# Termination_connector.net
KiCad netlist of a schematic drawn in Altium Designer
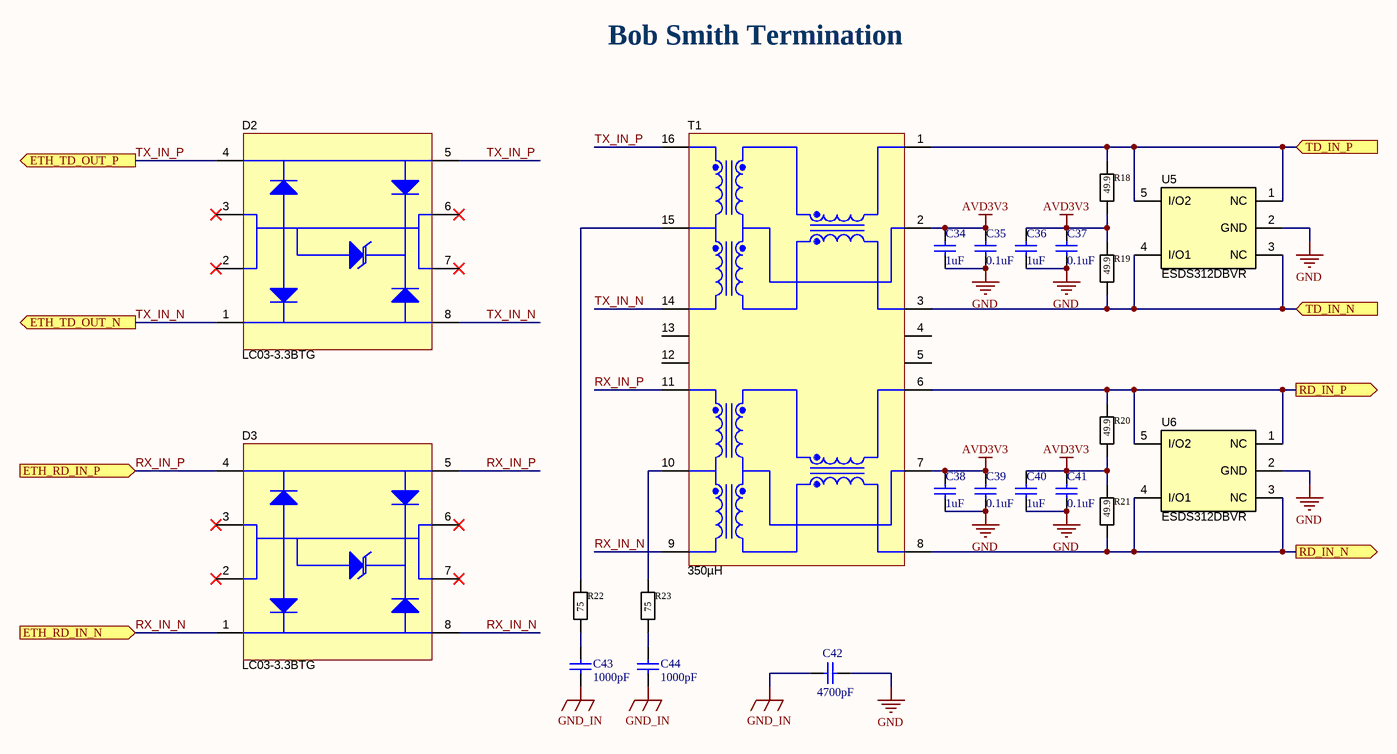
[diagram p0: Termination,connector.SchDoc]

(export (version "E")
  (design (tool "Eeschema 10.0.6"))
  (components
    (comp (ref "C34")
      (value "1uF")
      (footprint "CAPC1005X61USR")
      (description "CAP CER 1UF 16V X5R 0402")
      (fields
        (field (name "MANUFACTURER") "Samsung Electro-Mechanics")
        (field (name "MANUFACTURER PART NUMBER") "CL05A105KO5NNNC")
      )
      (libsource (lib "AA-Design-Challenge") (part "Cap"))
    )
    (comp (ref "C35")
      (value "0.1uF")
      (footprint "CAPC1005X61USR")
      (description "CAP CER 0.1UF 50V X7R 0402")
      (fields
        (field (name "MANUFACTURER") "TDK Corporation")
        (field (name "MANUFACTURER PART NUMBER") "CGA2B3X7R1H104K050BB")
      )
      (libsource (lib "AA-Design-Challenge") (part "Cap"))
    )
    (comp (ref "C36")
      (value "1uF")
      (footprint "CAPC1005X61USR")
      (description "CAP CER 1UF 16V X5R 0402")
      (fields
        (field (name "MANUFACTURER") "Samsung Electro-Mechanics")
        (field (name "MANUFACTURER PART NUMBER") "CL05A105KO5NNNC")
      )
      (libsource (lib "AA-Design-Challenge") (part "Cap"))
    )
    (comp (ref "C37")
      (value "0.1uF")
      (footprint "CAPC1005X61USR")
      (description "CAP CER 0.1UF 50V X7R 0402")
      (fields
        (field (name "MANUFACTURER") "TDK Corporation")
        (field (name "MANUFACTURER PART NUMBER") "CGA2B3X7R1H104K050BB")
      )
      (libsource (lib "AA-Design-Challenge") (part "Cap"))
    )
    (comp (ref "C38")
      (value "1uF")
      (footprint "CAPC1005X61USR")
      (description "CAP CER 1UF 16V X5R 0402")
      (fields
        (field (name "MANUFACTURER") "Samsung Electro-Mechanics")
        (field (name "MANUFACTURER PART NUMBER") "CL05A105KO5NNNC")
      )
      (libsource (lib "AA-Design-Challenge") (part "Cap"))
    )
    (comp (ref "C39")
      (value "0.1uF")
      (footprint "CAPC1005X61USR")
      (description "CAP CER 0.1UF 50V X7R 0402")
      (fields
        (field (name "MANUFACTURER") "TDK Corporation")
        (field (name "MANUFACTURER PART NUMBER") "CGA2B3X7R1H104K050BB")
      )
      (libsource (lib "AA-Design-Challenge") (part "Cap"))
    )
    (comp (ref "C40")
      (value "1uF")
      (footprint "CAPC1005X61USR")
      (description "CAP CER 1UF 16V X5R 0402")
      (fields
        (field (name "MANUFACTURER") "Samsung Electro-Mechanics")
        (field (name "MANUFACTURER PART NUMBER") "CL05A105KO5NNNC")
      )
      (libsource (lib "AA-Design-Challenge") (part "Cap"))
    )
    (comp (ref "C41")
      (value "0.1uF")
      (footprint "CAPC1005X61USR")
      (description "CAP CER 0.1UF 50V X7R 0402")
      (fields
        (field (name "MANUFACTURER") "TDK Corporation")
        (field (name "MANUFACTURER PART NUMBER") "CGA2B3X7R1H104K050BB")
      )
      (libsource (lib "AA-Design-Challenge") (part "Cap"))
    )
    (comp (ref "C42")
      (value "4700pF")
      (footprint "CAPC4532X200N")
      (description "CAP CER 4700PF 2KV X7R 1812")
      (fields
        (field (name "MANUFACTURER") "Murata Electronics")
        (field (name "MANUFACTURER PART NUMBER") "GR443DR73D472KW01L")
      )
      (libsource (lib "AA-Design-Challenge") (part "Cap"))
    )
    (comp (ref "C43")
      (value "1000pF")
      (footprint "CAPC1005X61USR")
      (description "CAP CER 1000PF 25V X7R 0402")
      (fields
        (field (name "MANUFACTURER") "KEMET")
        (field (name "MANUFACTURER PART NUMBER") "C0402C102K3RACTU")
      )
      (libsource (lib "AA-Design-Challenge") (part "Cap"))
    )
    (comp (ref "C44")
      (value "1000pF")
      (footprint "CAPC1005X61USR")
      (description "CAP CER 1000PF 25V X7R 0402")
      (fields
        (field (name "MANUFACTURER") "KEMET")
        (field (name "MANUFACTURER PART NUMBER") "C0402C102K3RACTU")
      )
      (libsource (lib "AA-Design-Challenge") (part "Cap"))
    )
    (comp (ref "D2")
      (value "LC03-3.3BTG")
      (footprint "SOIC127P600X175-8N")
      (description "Diode, TVS, Uni, 3.3 V, 17 Vc, 3300 W, 150 A, SOIC-8")
      (fields (field (name "MANUFACTURER") "Littelfuse"))
      (libsource (lib "AA-Design-Challenge") (part "CMP-0085616-1"))
    )
    (comp (ref "D3")
      (value "LC03-3.3BTG")
      (footprint "SOIC127P600X175-8N")
      (description "Diode, TVS, Uni, 3.3 V, 17 Vc, 3300 W, 150 A, SOIC-8")
      (fields (field (name "MANUFACTURER") "Littelfuse"))
      (libsource (lib "AA-Design-Challenge") (part "CMP-0085616-1"))
    )
    (comp (ref "R18")
      (value "49.9")
      (footprint "RESC1005X40USR")
      (description "RES SMD 49.9 OHM 1% 1/16W 0402")
      (fields
        (field (name "MANUFACTURER") "Yageo")
        (field (name "MANUFACTURER PART NUMBER") "RC0402FR-0749R9L")
      )
      (libsource (lib "AA-Design-Challenge") (part "R"))
    )
    (comp (ref "R19")
      (value "49.9")
      (footprint "RESC1005X40USR")
      (description "RES SMD 49.9 OHM 1% 1/16W 0402")
      (fields
        (field (name "MANUFACTURER") "Yageo")
        (field (name "MANUFACTURER PART NUMBER") "RC0402FR-0749R9L")
      )
      (libsource (lib "AA-Design-Challenge") (part "R"))
    )
    (comp (ref "R20")
      (value "49.9")
      (footprint "RESC1005X40USR")
      (description "RES SMD 49.9 OHM 1% 1/16W 0402")
      (fields
        (field (name "MANUFACTURER") "Yageo")
        (field (name "MANUFACTURER PART NUMBER") "RC0402FR-0749R9L")
      )
      (libsource (lib "AA-Design-Challenge") (part "R"))
    )
    (comp (ref "R21")
      (value "49.9")
      (footprint "RESC1005X40USR")
      (description "RES SMD 49.9 OHM 1% 1/16W 0402")
      (fields
        (field (name "MANUFACTURER") "Yageo")
        (field (name "MANUFACTURER PART NUMBER") "RC0402FR-0749R9L")
      )
      (libsource (lib "AA-Design-Challenge") (part "R"))
    )
    (comp (ref "R22")
      (value "75")
      (footprint "RESC1005X40USR")
      (description "RES SMD 75 OHM 1% 1/10W 0402")
      (fields
        (field (name "MANUFACTURER") "Panasonic Electronic Components")
        (field (name "MANUFACTURER PART NUMBER") "ERJ-2RKF75R0X")
      )
      (libsource (lib "AA-Design-Challenge") (part "R"))
    )
    (comp (ref "R23")
      (value "75")
      (footprint "RESC1005X40USR")
      (description "RES SMD 75 OHM 1% 1/10W 0402")
      (fields
        (field (name "MANUFACTURER") "Panasonic Electronic Components")
        (field (name "MANUFACTURER PART NUMBER") "ERJ-2RKF75R0X")
      )
      (libsource (lib "AA-Design-Challenge") (part "R"))
    )
    (comp (ref "T1")
      (value "~")
      (footprint "HX1198FNLT_PUL")
      (description "Transformer, 350 uH, SMT")
      (fields
        (field (name "MANUFACTURER PART NUMBER") "HX1198FNLT")
        (field (name "VALUEDISPLAYED") "350µH")
        (field (name "MANUFACTURER") "Pulse Engineering")
        (field (name "SYMBOLCREATOR") "Altium")
        (field (name "PUBLISHER") "Texas Instruments")
      )
      (libsource (lib "AA-Design-Challenge") (part "HX1198FNLT"))
    )
    (comp (ref "U5")
      (value "ESDS312DBVR")
      (footprint "SOT23-5")
      (description "FAMILY OF UNI-DIRECTIONAL SURGE")
      (fields
        (field (name "DIGI-KEY PART NUMBER") "296-51112-2-ND")
        (field (name "MANUFACTURER") "Texas Instruments")
        (field (name "MANUFACTURER PART NUMBER") "ESDS312DBVR")
      )
      (libsource (lib "AA-Design-Challenge") (part "ESDS312DBVR"))
    )
    (comp (ref "U6")
      (value "ESDS312DBVR")
      (footprint "SOT23-5")
      (description "FAMILY OF UNI-DIRECTIONAL SURGE")
      (fields
        (field (name "DIGI-KEY PART NUMBER") "296-51112-2-ND")
        (field (name "MANUFACTURER") "Texas Instruments")
        (field (name "MANUFACTURER PART NUMBER") "ESDS312DBVR")
      )
      (libsource (lib "AA-Design-Challenge") (part "ESDS312DBVR"))
    )
  )
  (nets
    (net (code "1") (name "/RD_IN_N") (class "Default")
      (node (ref "R21") (pin "2") (pintype "passive"))
      (node (ref "T1") (pin "8") (pinfunction "RD-_8") (pintype "passive"))
      (node (ref "U6") (pin "3") (pinfunction "NC_3") (pintype "passive"))
      (node (ref "U6") (pin "4") (pinfunction "I/O1_4") (pintype "passive"))
    )
    (net (code "2") (name "/RD_IN_P") (class "Default")
      (node (ref "R20") (pin "1") (pintype "passive"))
      (node (ref "T1") (pin "6") (pinfunction "RD+_6") (pintype "passive"))
      (node (ref "U6") (pin "1") (pinfunction "NC_1") (pintype "passive"))
      (node (ref "U6") (pin "5") (pinfunction "I/O2_5") (pintype "passive"))
    )
    (net (code "3") (name "/RX_IN_N") (class "Default")
      (node (ref "D3") (pin "1") (pinfunction "1_1") (pintype "passive"))
      (node (ref "D3") (pin "8") (pinfunction "8_8") (pintype "passive"))
      (node (ref "T1") (pin "9") (pinfunction "RX-_9") (pintype "passive"))
    )
    (net (code "4") (name "/RX_IN_P") (class "Default")
      (node (ref "D3") (pin "4") (pinfunction "4_4") (pintype "passive"))
      (node (ref "D3") (pin "5") (pinfunction "5_5") (pintype "passive"))
      (node (ref "T1") (pin "11") (pinfunction "RX+_11") (pintype "passive"))
    )
    (net (code "5") (name "/TD_IN_N") (class "Default")
      (node (ref "R19") (pin "2") (pintype "passive"))
      (node (ref "T1") (pin "3") (pinfunction "TD-_3") (pintype "passive"))
      (node (ref "U5") (pin "3") (pinfunction "NC_3") (pintype "passive"))
      (node (ref "U5") (pin "4") (pinfunction "I/O1_4") (pintype "passive"))
    )
    (net (code "6") (name "/TD_IN_P") (class "Default")
      (node (ref "R18") (pin "1") (pintype "passive"))
      (node (ref "T1") (pin "1") (pinfunction "TD+_1") (pintype "passive"))
      (node (ref "U5") (pin "1") (pinfunction "NC_1") (pintype "passive"))
      (node (ref "U5") (pin "5") (pinfunction "I/O2_5") (pintype "passive"))
    )
    (net (code "7") (name "/TX_IN_N") (class "Default")
      (node (ref "D2") (pin "1") (pinfunction "1_1") (pintype "passive"))
      (node (ref "D2") (pin "8") (pinfunction "8_8") (pintype "passive"))
      (node (ref "T1") (pin "14") (pinfunction "TX-_14") (pintype "passive"))
    )
    (net (code "8") (name "/TX_IN_P") (class "Default")
      (node (ref "D2") (pin "4") (pinfunction "4_4") (pintype "passive"))
      (node (ref "D2") (pin "5") (pinfunction "5_5") (pintype "passive"))
      (node (ref "T1") (pin "16") (pinfunction "TX+_16") (pintype "passive"))
    )
    (net (code "9") (name "AVD3V3") (class "Default")
      (node (ref "C34") (pin "2") (pinfunction "2_2") (pintype "passive"))
      (node (ref "C35") (pin "1") (pinfunction "1_1") (pintype "passive"))
      (node (ref "C36") (pin "2") (pinfunction "2_2") (pintype "passive"))
      (node (ref "C37") (pin "1") (pinfunction "1_1") (pintype "passive"))
      (node (ref "C38") (pin "2") (pinfunction "2_2") (pintype "passive"))
      (node (ref "C39") (pin "1") (pinfunction "1_1") (pintype "passive"))
      (node (ref "C40") (pin "2") (pinfunction "2_2") (pintype "passive"))
      (node (ref "C41") (pin "1") (pinfunction "1_1") (pintype "passive"))
      (node (ref "R18") (pin "2") (pintype "passive"))
      (node (ref "R19") (pin "1") (pintype "passive"))
      (node (ref "R20") (pin "2") (pintype "passive"))
      (node (ref "R21") (pin "1") (pintype "passive"))
      (node (ref "T1") (pin "2") (pinfunction "TCT_2") (pintype "passive"))
      (node (ref "T1") (pin "7") (pinfunction "RCT_7") (pintype "passive"))
    )
    (net (code "10") (name "GND") (class "Default")
      (node (ref "C34") (pin "1") (pinfunction "1_1") (pintype "passive"))
      (node (ref "C35") (pin "2") (pinfunction "2_2") (pintype "passive"))
      (node (ref "C36") (pin "1") (pinfunction "1_1") (pintype "passive"))
      (node (ref "C37") (pin "2") (pinfunction "2_2") (pintype "passive"))
      (node (ref "C38") (pin "1") (pinfunction "1_1") (pintype "passive"))
      (node (ref "C39") (pin "2") (pinfunction "2_2") (pintype "passive"))
      (node (ref "C40") (pin "1") (pinfunction "1_1") (pintype "passive"))
      (node (ref "C41") (pin "2") (pinfunction "2_2") (pintype "passive"))
      (node (ref "C42") (pin "1") (pinfunction "1_1") (pintype "passive"))
      (node (ref "U5") (pin "2") (pinfunction "GND_2") (pintype "passive"))
      (node (ref "U6") (pin "2") (pinfunction "GND_2") (pintype "passive"))
    )
    (net (code "11") (name "GND_IN") (class "Default")
      (node (ref "C42") (pin "2") (pinfunction "2_2") (pintype "passive"))
      (node (ref "C43") (pin "1") (pinfunction "1_1") (pintype "passive"))
      (node (ref "C44") (pin "1") (pinfunction "1_1") (pintype "passive"))
    )
    (net (code "12") (name "Net-(C43-Pad2)") (class "Default")
      (node (ref "C43") (pin "2") (pinfunction "2_2") (pintype "passive"))
      (node (ref "R22") (pin "2") (pintype "passive"))
    )
    (net (code "13") (name "Net-(C44-Pad2)") (class "Default")
      (node (ref "C44") (pin "2") (pinfunction "2_2") (pintype "passive"))
      (node (ref "R23") (pin "2") (pintype "passive"))
    )
    (net (code "14") (name "Net-(R22-Pad1)") (class "Default")
      (node (ref "R22") (pin "1") (pintype "passive"))
      (node (ref "T1") (pin "15") (pinfunction "CMT_15") (pintype "passive"))
    )
    (net (code "15") (name "Net-(R23-Pad1)") (class "Default")
      (node (ref "R23") (pin "1") (pintype "passive"))
      (node (ref "T1") (pin "10") (pinfunction "CMT_10") (pintype "passive"))
    )
    (net (code "16") (name "unconnected-(D2-Pad2)") (class "Default")
      (node (ref "D2") (pin "2") (pinfunction "2_2") (pintype "passive+no_connect"))
    )
    (net (code "17") (name "unconnected-(D2-Pad3)") (class "Default")
      (node (ref "D2") (pin "3") (pinfunction "3_3") (pintype "passive+no_connect"))
    )
    (net (code "18") (name "unconnected-(D2-Pad6)") (class "Default")
      (node (ref "D2") (pin "6") (pinfunction "6_6") (pintype "passive+no_connect"))
    )
    (net (code "19") (name "unconnected-(D2-Pad7)") (class "Default")
      (node (ref "D2") (pin "7") (pinfunction "7_7") (pintype "passive+no_connect"))
    )
    (net (code "20") (name "unconnected-(D3-Pad2)") (class "Default")
      (node (ref "D3") (pin "2") (pinfunction "2_2") (pintype "passive+no_connect"))
    )
    (net (code "21") (name "unconnected-(D3-Pad3)") (class "Default")
      (node (ref "D3") (pin "3") (pinfunction "3_3") (pintype "passive+no_connect"))
    )
    (net (code "22") (name "unconnected-(D3-Pad6)") (class "Default")
      (node (ref "D3") (pin "6") (pinfunction "6_6") (pintype "passive+no_connect"))
    )
    (net (code "23") (name "unconnected-(D3-Pad7)") (class "Default")
      (node (ref "D3") (pin "7") (pinfunction "7_7") (pintype "passive+no_connect"))
    )
    (net (code "24") (name "unconnected-(T1-NC-Pad4)") (class "Default")
      (node (ref "T1") (pin "4") (pinfunction "NC_4") (pintype "passive"))
    )
    (net (code "25") (name "unconnected-(T1-NC-Pad5)") (class "Default")
      (node (ref "T1") (pin "5") (pinfunction "NC_5") (pintype "passive"))
    )
    (net (code "26") (name "unconnected-(T1-NC-Pad12)") (class "Default")
      (node (ref "T1") (pin "12") (pinfunction "NC_12") (pintype "passive"))
    )
    (net (code "27") (name "unconnected-(T1-NC-Pad13)") (class "Default")
      (node (ref "T1") (pin "13") (pinfunction "NC_13") (pintype "passive"))
    )
  )
)
